# lab2_ignatova_buck_boost.net
KiCad netlist of a schematic drawn in Altium Designer
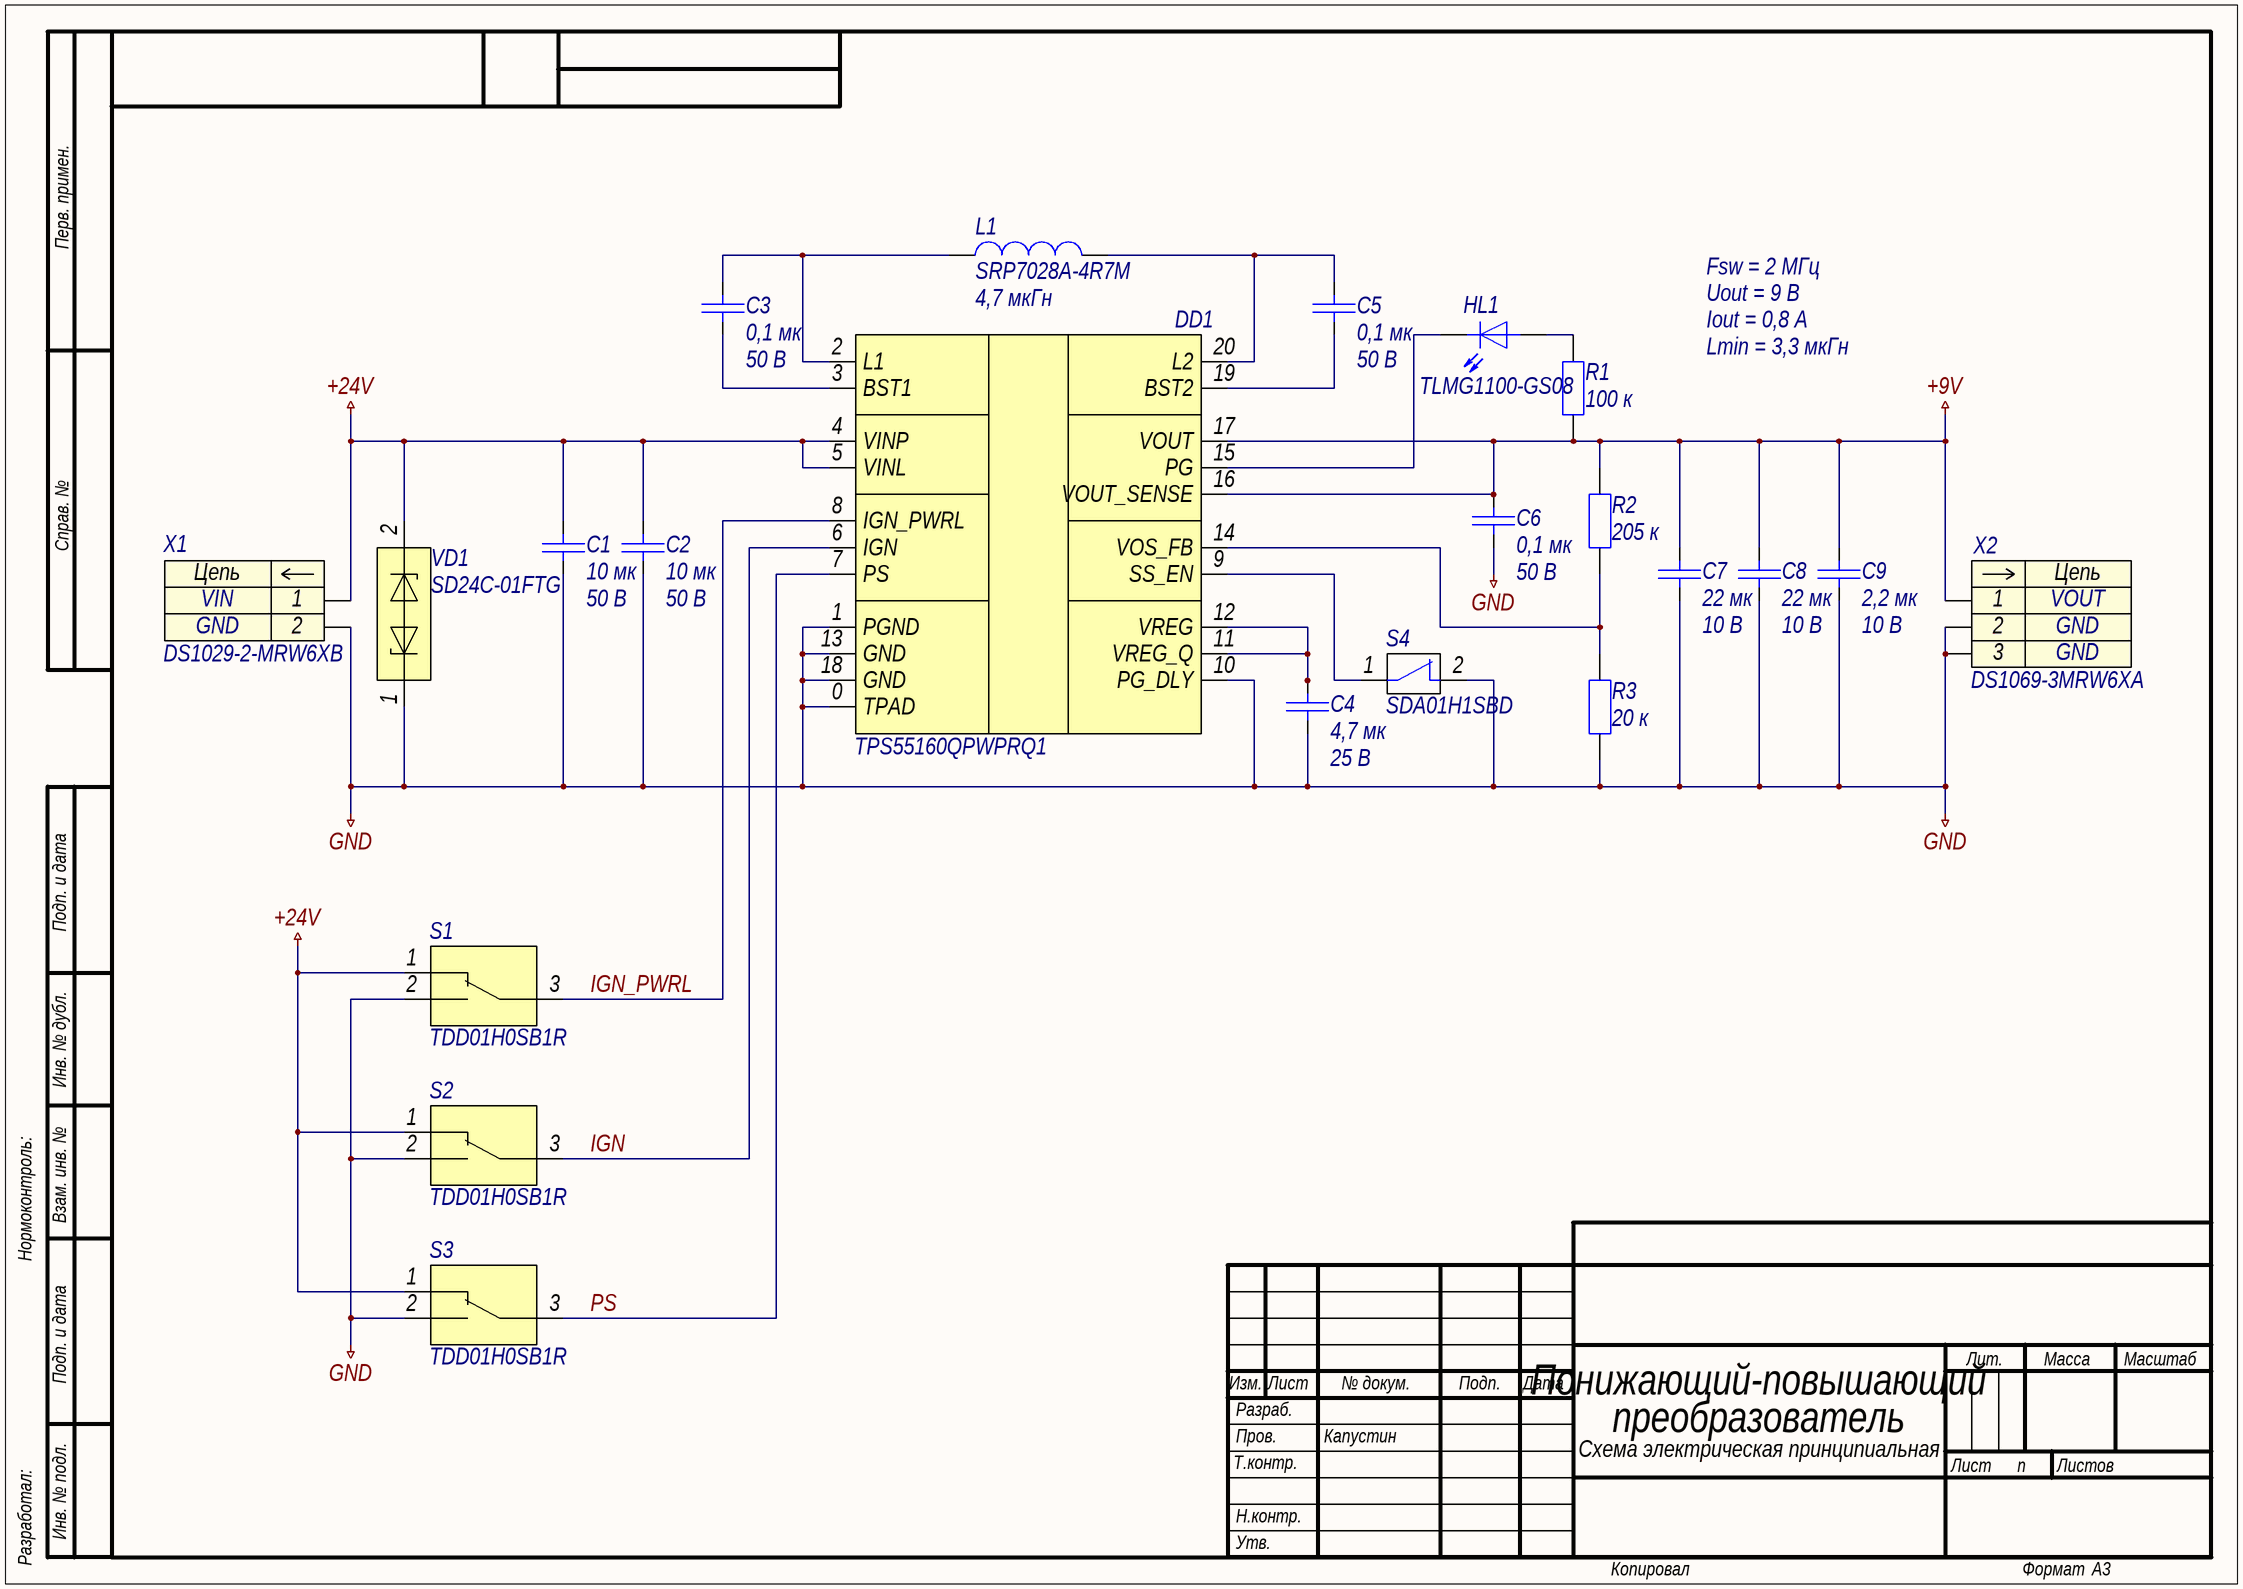
[diagram p0: lab2_ignatova_buck_boost.SchDoc]

(export (version "E")
  (design (tool "Eeschema 10.0.6"))
  (components
    (comp (ref "C1")
      (value "10 мк")
      (footprint "C1206")
      (description "=Описание")
      (fields (field (name "НАПРЯЖЕНИЕ") "50 В"))
      (libsource (lib "Database_Students") (part "C-NONPOLAR"))
    )
    (comp (ref "C2")
      (value "10 мк")
      (footprint "C1206")
      (description "=Описание")
      (fields (field (name "НАПРЯЖЕНИЕ") "50 В"))
      (libsource (lib "Database_Students") (part "C-NONPOLAR"))
    )
    (comp (ref "C3")
      (value "0,1 мк")
      (footprint "C0603")
      (description "=Описание")
      (fields (field (name "НАПРЯЖЕНИЕ") "50 В"))
      (libsource (lib "Database_Students") (part "C-NONPOLAR"))
    )
    (comp (ref "C4")
      (value "4,7 мк")
      (footprint "C0603")
      (description "=Описание")
      (fields (field (name "НАПРЯЖЕНИЕ") "25 В"))
      (libsource (lib "Database_Students") (part "C-NONPOLAR"))
    )
    (comp (ref "C5")
      (value "0,1 мк")
      (footprint "C0603")
      (description "=Описание")
      (fields (field (name "НАПРЯЖЕНИЕ") "50 В"))
      (libsource (lib "Database_Students") (part "C-NONPOLAR"))
    )
    (comp (ref "C6")
      (value "0,1 мк")
      (footprint "C0603")
      (description "=Описание")
      (fields (field (name "НАПРЯЖЕНИЕ") "50 В"))
      (libsource (lib "Database_Students") (part "C-NONPOLAR"))
    )
    (comp (ref "C7")
      (value "22 мк")
      (footprint "C0603")
      (description "=Описание")
      (fields (field (name "НАПРЯЖЕНИЕ") "10 В"))
      (libsource (lib "Database_Students") (part "C-NONPOLAR"))
    )
    (comp (ref "C8")
      (value "22 мк")
      (footprint "C0603")
      (description "=Описание")
      (fields (field (name "НАПРЯЖЕНИЕ") "10 В"))
      (libsource (lib "Database_Students") (part "C-NONPOLAR"))
    )
    (comp (ref "C9")
      (value "2,2 мк")
      (footprint "C0603")
      (description "=Описание")
      (fields (field (name "НАПРЯЖЕНИЕ") "10 В"))
      (libsource (lib "Database_Students") (part "C-NONPOLAR"))
    )
    (comp (ref "DD1")
      (value "TPS55160QPWPRQ1")
      (footprint "HTSSOP-20")
      (description "=Описание")
      (libsource (lib "Database_Students") (part "TPS55160QPWPRQ1"))
    )
    (comp (ref "HL1")
      (value "TLMG1100-GS08")
      (footprint "HL0603")
      (description "=Описание")
      (libsource (lib "Database_Students") (part "HL-COMMON"))
    )
    (comp (ref "L1")
      (value "SRP7028A-4R7M")
      (footprint "SRP-2-730X660X280")
      (description "=Описание")
      (fields (field (name "ИНДУКТИВНОСТЬ") "4,7 мкГн"))
      (libsource (lib "Database_Students") (part "INDUCTOR-COMMON"))
    )
    (comp (ref "R1")
      (value "100 к")
      (footprint "R0603")
      (description "=Описание")
      (libsource (lib "Database_Students") (part "R-COMMON"))
    )
    (comp (ref "R2")
      (value "205 к")
      (footprint "R0603")
      (description "=Описание")
      (libsource (lib "Database_Students") (part "R-COMMON"))
    )
    (comp (ref "R3")
      (value "20 к")
      (footprint "R0603")
      (description "=Описание")
      (libsource (lib "Database_Students") (part "R-COMMON"))
    )
    (comp (ref "S1")
      (value "TDD01H0SB1R")
      (footprint "TDD01H0SB1R")
      (description "=Описание")
      (libsource (lib "Database_Students") (part "SWITCH-3C"))
    )
    (comp (ref "S2")
      (value "TDD01H0SB1R")
      (footprint "TDD01H0SB1R")
      (description "=Описание")
      (libsource (lib "Database_Students") (part "SWITCH-3C"))
    )
    (comp (ref "S3")
      (value "TDD01H0SB1R")
      (footprint "TDD01H0SB1R")
      (description "=Описание")
      (libsource (lib "Database_Students") (part "SWITCH-3C"))
    )
    (comp (ref "S4")
      (value "SDA01H1SBD")
      (footprint "SDA01H1SBD")
      (description "=Описание")
      (libsource (lib "Database_Students") (part "SWITCH-2C"))
    )
    (comp (ref "VD1")
      (value "SD24C-01FTG")
      (footprint "SOD-323")
      (description "=Описание")
      (libsource (lib "Database_Students") (part "ZENER-BI-DIRECTIONAL"))
    )
    (comp (ref "X1")
      (value "DS1029-2-MRW6XB")
      (footprint "DS1029-2-MRW6XB")
      (description "=Описание")
      (libsource (lib "Database_Students") (part "HEADER-2-PLG"))
    )
    (comp (ref "X2")
      (value "DS1069-3MRW6XA")
      (footprint "DS1069-3MRW6XA")
      (description "=Описание")
      (libsource (lib "Database_Students") (part "HEADER-3-PLG"))
    )
  )
  (nets
    (net (code "1") (name "+9V") (class "Default")
      (node (ref "C6") (pin "1") (pinfunction "1_1") (pintype "passive"))
      (node (ref "C7") (pin "1") (pinfunction "1_1") (pintype "passive"))
      (node (ref "C8") (pin "1") (pinfunction "1_1") (pintype "passive"))
      (node (ref "C9") (pin "1") (pinfunction "1_1") (pintype "passive"))
      (node (ref "DD1") (pin "16") (pinfunction "VOUT_SENSE_16") (pintype "passive"))
      (node (ref "DD1") (pin "17") (pinfunction "VOUT_17") (pintype "passive"))
      (node (ref "R1") (pin "2") (pinfunction "2_2") (pintype "passive"))
      (node (ref "R2") (pin "2") (pinfunction "2_2") (pintype "passive"))
      (node (ref "X2") (pin "1") (pinfunction "1_1") (pintype "passive"))
    )
    (net (code "2") (name "+24V") (class "Default")
      (node (ref "C1") (pin "1") (pinfunction "1_1") (pintype "passive"))
      (node (ref "C2") (pin "1") (pinfunction "1_1") (pintype "passive"))
      (node (ref "DD1") (pin "4") (pinfunction "VINP_4") (pintype "passive"))
      (node (ref "DD1") (pin "5") (pinfunction "VINL_5") (pintype "passive"))
      (node (ref "S1") (pin "1") (pinfunction "1_1") (pintype "passive"))
      (node (ref "S2") (pin "1") (pinfunction "1_1") (pintype "passive"))
      (node (ref "S3") (pin "1") (pinfunction "1_1") (pintype "passive"))
      (node (ref "VD1") (pin "2") (pinfunction "2_2") (pintype "passive"))
      (node (ref "X1") (pin "1") (pinfunction "1_1") (pintype "passive"))
    )
    (net (code "3") (name "/IGN") (class "Default")
      (node (ref "DD1") (pin "6") (pinfunction "IGN_6") (pintype "passive"))
      (node (ref "S2") (pin "3") (pinfunction "3_3") (pintype "passive"))
    )
    (net (code "4") (name "/IGN_PWRL") (class "Default")
      (node (ref "DD1") (pin "8") (pinfunction "IGN_PWRL_8") (pintype "passive"))
      (node (ref "S1") (pin "3") (pinfunction "3_3") (pintype "passive"))
    )
    (net (code "5") (name "/PS") (class "Default")
      (node (ref "DD1") (pin "7") (pinfunction "PS_7") (pintype "passive"))
      (node (ref "S3") (pin "3") (pinfunction "3_3") (pintype "passive"))
    )
    (net (code "6") (name "GND") (class "Default")
      (node (ref "C1") (pin "2") (pinfunction "2_2") (pintype "passive"))
      (node (ref "C2") (pin "2") (pinfunction "2_2") (pintype "passive"))
      (node (ref "C4") (pin "2") (pinfunction "2_2") (pintype "passive"))
      (node (ref "C6") (pin "2") (pinfunction "2_2") (pintype "passive"))
      (node (ref "C7") (pin "2") (pinfunction "2_2") (pintype "passive"))
      (node (ref "C8") (pin "2") (pinfunction "2_2") (pintype "passive"))
      (node (ref "C9") (pin "2") (pinfunction "2_2") (pintype "passive"))
      (node (ref "DD1") (pin "0") (pinfunction "TPAD_0") (pintype "passive"))
      (node (ref "DD1") (pin "1") (pinfunction "PGND_1") (pintype "passive"))
      (node (ref "DD1") (pin "10") (pinfunction "PG_DLY_10") (pintype "passive"))
      (node (ref "DD1") (pin "13") (pinfunction "GND_13") (pintype "passive"))
      (node (ref "DD1") (pin "18") (pinfunction "GND_18") (pintype "passive"))
      (node (ref "R3") (pin "1") (pinfunction "1_1") (pintype "passive"))
      (node (ref "S1") (pin "2") (pinfunction "2_2") (pintype "passive"))
      (node (ref "S2") (pin "2") (pinfunction "2_2") (pintype "passive"))
      (node (ref "S3") (pin "2") (pinfunction "2_2") (pintype "passive"))
      (node (ref "S4") (pin "2") (pinfunction "2_2") (pintype "passive"))
      (node (ref "VD1") (pin "1") (pinfunction "1_1") (pintype "passive"))
      (node (ref "X1") (pin "2") (pinfunction "2_2") (pintype "passive"))
      (node (ref "X2") (pin "2") (pinfunction "2_2") (pintype "passive"))
      (node (ref "X2") (pin "3") (pinfunction "3_3") (pintype "passive"))
    )
    (net (code "7") (name "Net-(DD1-BST1)") (class "Default")
      (node (ref "C3") (pin "2") (pinfunction "2_2") (pintype "passive"))
      (node (ref "DD1") (pin "3") (pinfunction "BST1_3") (pintype "passive"))
    )
    (net (code "8") (name "Net-(DD1-BST2)") (class "Default")
      (node (ref "C5") (pin "2") (pinfunction "2_2") (pintype "passive"))
      (node (ref "DD1") (pin "19") (pinfunction "BST2_19") (pintype "passive"))
    )
    (net (code "9") (name "Net-(DD1-L1)") (class "Default")
      (node (ref "C3") (pin "1") (pinfunction "1_1") (pintype "passive"))
      (node (ref "DD1") (pin "2") (pinfunction "L1_2") (pintype "passive"))
      (node (ref "L1") (pin "1") (pinfunction "1_1") (pintype "passive"))
    )
    (net (code "10") (name "Net-(DD1-L2)") (class "Default")
      (node (ref "C5") (pin "1") (pinfunction "1_1") (pintype "passive"))
      (node (ref "DD1") (pin "20") (pinfunction "L2_20") (pintype "passive"))
      (node (ref "L1") (pin "2") (pinfunction "2_2") (pintype "passive"))
    )
    (net (code "11") (name "Net-(DD1-PG)") (class "Default")
      (node (ref "DD1") (pin "15") (pinfunction "PG_15") (pintype "passive"))
      (node (ref "HL1") (pin "1") (pinfunction "1_1") (pintype "passive"))
    )
    (net (code "12") (name "Net-(DD1-SS_EN)") (class "Default")
      (node (ref "DD1") (pin "9") (pinfunction "SS_EN_9") (pintype "passive"))
      (node (ref "S4") (pin "1") (pinfunction "1_1") (pintype "passive"))
    )
    (net (code "13") (name "Net-(DD1-VOS_FB)") (class "Default")
      (node (ref "DD1") (pin "14") (pinfunction "VOS_FB_14") (pintype "passive"))
      (node (ref "R2") (pin "1") (pinfunction "1_1") (pintype "passive"))
      (node (ref "R3") (pin "2") (pinfunction "2_2") (pintype "passive"))
    )
    (net (code "14") (name "Net-(DD1-VREG)") (class "Default")
      (node (ref "C4") (pin "1") (pinfunction "1_1") (pintype "passive"))
      (node (ref "DD1") (pin "11") (pinfunction "VREG_Q_11") (pintype "passive"))
      (node (ref "DD1") (pin "12") (pinfunction "VREG_12") (pintype "passive"))
    )
    (net (code "15") (name "Net-(HL1-Pad2)") (class "Default")
      (node (ref "HL1") (pin "2") (pinfunction "2_2") (pintype "passive"))
      (node (ref "R1") (pin "1") (pinfunction "1_1") (pintype "passive"))
    )
  )
)
